# Connectors.net
KiCad netlist of a schematic drawn in Altium Designer
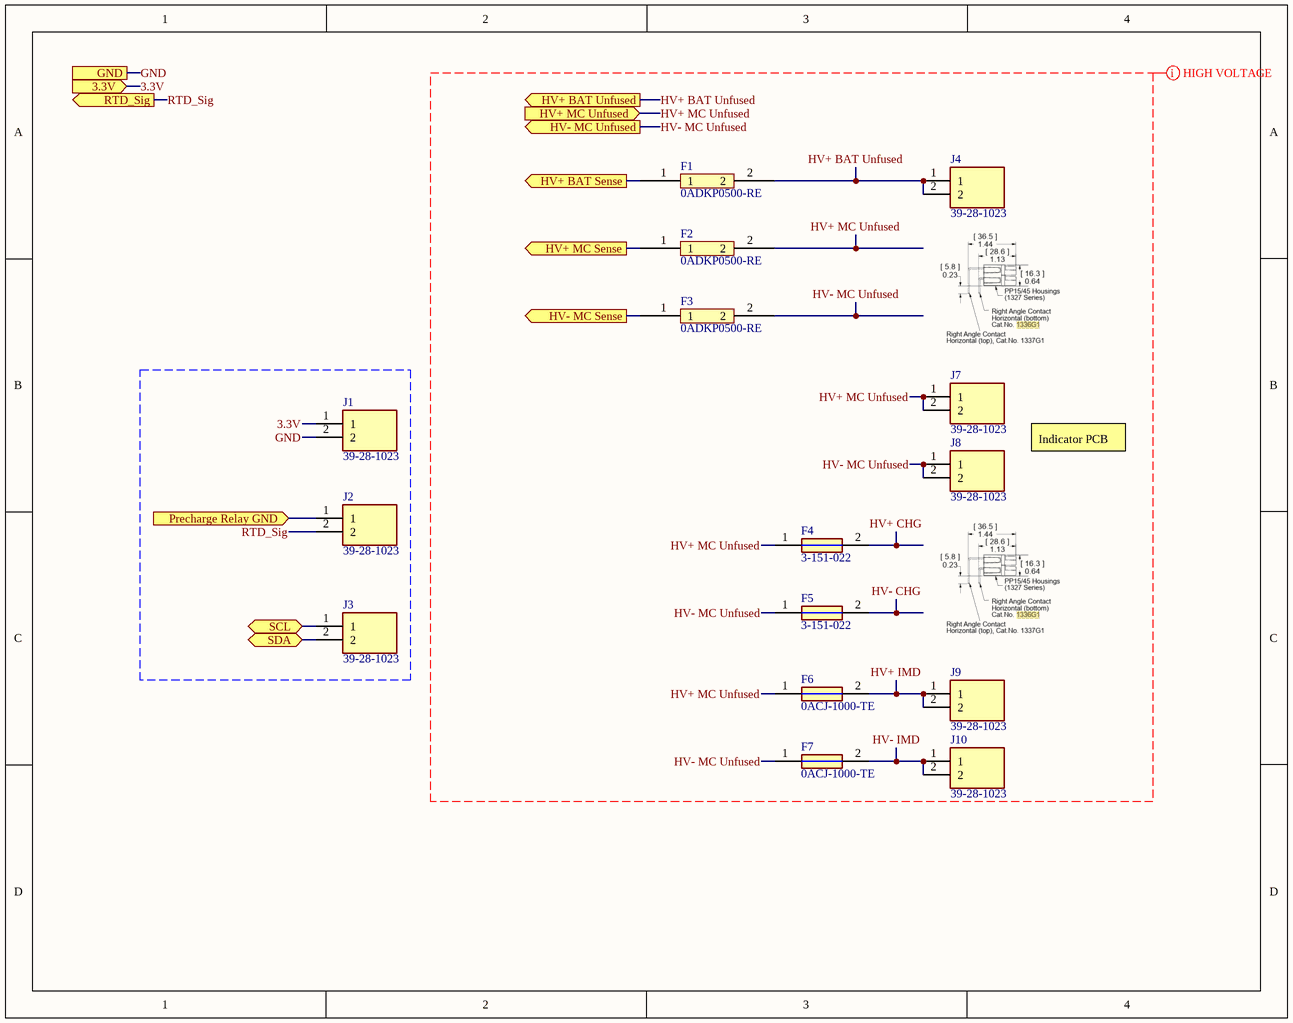
[diagram p0: Connectors.SchDoc]

(export (version "E")
  (design (tool "Eeschema 10.0.6"))
  (components
    (comp (ref "F1")
      (value "0ADKP0500-RE")
      (footprint "0ADKP0500-RE")
      (description "Fuse")
      (libsource (lib "SamacSys") (part "0ADKP0500-RE"))
    )
    (comp (ref "F2")
      (value "0ADKP0500-RE")
      (footprint "0ADKP0500-RE")
      (description "Fuse")
      (libsource (lib "SamacSys") (part "0ADKP0500-RE"))
    )
    (comp (ref "F3")
      (value "0ADKP0500-RE")
      (footprint "0ADKP0500-RE")
      (description "Fuse")
      (libsource (lib "SamacSys") (part "0ADKP0500-RE"))
    )
    (comp (ref "F4")
      (value "3-151-022")
      (footprint "SamacSys:3151022")
      (description "Fuse")
      (libsource (lib "SamacSys") (part "3-151-022"))
    )
    (comp (ref "F5")
      (value "3-151-022")
      (footprint "SamacSys:3151022")
      (description "Fuse")
      (libsource (lib "SamacSys") (part "3-151-022"))
    )
    (comp (ref "F6")
      (value "0ACJ-1000-TE")
      (footprint "FUSC13250X555N")
      (description "Fuse")
      (fields (field (name "MOUSER PART NUMBER") "530-0ACJ-1000-TE"))
      (libsource (lib "SamacSys") (part "0ACJ-1000-TE"))
    )
    (comp (ref "F7")
      (value "0ACJ-1000-TE")
      (footprint "FUSC13250X555N")
      (description "Fuse")
      (fields (field (name "MOUSER PART NUMBER") "530-0ACJ-1000-TE"))
      (libsource (lib "SamacSys") (part "0ACJ-1000-TE"))
    )
    (comp (ref "J1")
      (value "39-28-1023")
      (footprint "SamacSys:39-28-1023")
      (description "Connector")
      (fields (field (name "MOUSER PART NUMBER") "538-39-28-1023"))
      (libsource (lib "SamacSys") (part "39-28-1023"))
    )
    (comp (ref "J2")
      (value "39-28-1023")
      (footprint "SamacSys:39-28-1023")
      (description "Connector")
      (fields (field (name "MOUSER PART NUMBER") "538-39-28-1023"))
      (libsource (lib "SamacSys") (part "39-28-1023"))
    )
    (comp (ref "J3")
      (value "39-28-1023")
      (footprint "SamacSys:39-28-1023")
      (description "Connector")
      (fields (field (name "MOUSER PART NUMBER") "538-39-28-1023"))
      (libsource (lib "SamacSys") (part "39-28-1023"))
    )
    (comp (ref "J4")
      (value "39-28-1023")
      (footprint "SamacSys:39-28-1023")
      (description "Connector")
      (fields (field (name "MOUSER PART NUMBER") "538-39-28-1023"))
      (libsource (lib "SamacSys") (part "39-28-1023"))
    )
    (comp (ref "J7")
      (value "39-28-1023")
      (footprint "SamacSys:39-28-1023")
      (description "Connector")
      (fields (field (name "MOUSER PART NUMBER") "538-39-28-1023"))
      (libsource (lib "SamacSys") (part "39-28-1023"))
    )
    (comp (ref "J8")
      (value "39-28-1023")
      (footprint "SamacSys:39-28-1023")
      (description "Connector")
      (fields (field (name "MOUSER PART NUMBER") "538-39-28-1023"))
      (libsource (lib "SamacSys") (part "39-28-1023"))
    )
    (comp (ref "J9")
      (value "39-28-1023")
      (footprint "SamacSys:39-28-1023")
      (description "Connector")
      (fields (field (name "MOUSER PART NUMBER") "538-39-28-1023"))
      (libsource (lib "SamacSys") (part "39-28-1023"))
    )
    (comp (ref "J10")
      (value "39-28-1023")
      (footprint "SamacSys:39-28-1023")
      (description "Connector")
      (fields (field (name "MOUSER PART NUMBER") "538-39-28-1023"))
      (libsource (lib "SamacSys") (part "39-28-1023"))
    )
  )
  (nets
    (net (code "1") (name "/3.3V") (class "Default")
      (node (ref "J1") (pin "1") (pinfunction "1_1") (pintype "passive"))
    )
    (net (code "2") (name "/GND") (class "Default")
      (node (ref "J1") (pin "2") (pinfunction "2_2") (pintype "passive"))
    )
    (net (code "3") (name "/HV+ BAT Sense") (class "Default")
      (node (ref "F1") (pin "1") (pinfunction "1_1") (pintype "passive"))
    )
    (net (code "4") (name "/HV+ BAT Unfused") (class "Default")
      (node (ref "F1") (pin "2") (pinfunction "2_2") (pintype "passive"))
      (node (ref "J4") (pin "1") (pinfunction "1_1") (pintype "passive"))
      (node (ref "J4") (pin "2") (pinfunction "2_2") (pintype "passive"))
    )
    (net (code "5") (name "/HV+ CHG") (class "Default")
      (node (ref "F4") (pin "2") (pinfunction "2_2") (pintype "passive"))
    )
    (net (code "6") (name "/HV+ IMD") (class "Default")
      (node (ref "F6") (pin "2") (pinfunction "2_2") (pintype "passive"))
      (node (ref "J9") (pin "1") (pinfunction "1_1") (pintype "passive"))
      (node (ref "J9") (pin "2") (pinfunction "2_2") (pintype "passive"))
    )
    (net (code "7") (name "/HV+ MC Sense") (class "Default")
      (node (ref "F2") (pin "1") (pinfunction "1_1") (pintype "passive"))
    )
    (net (code "8") (name "/HV+ MC Unfused") (class "Default")
      (node (ref "F2") (pin "2") (pinfunction "2_2") (pintype "passive"))
      (node (ref "F4") (pin "1") (pinfunction "1_1") (pintype "passive"))
      (node (ref "F6") (pin "1") (pinfunction "1_1") (pintype "passive"))
      (node (ref "J7") (pin "1") (pinfunction "1_1") (pintype "passive"))
      (node (ref "J7") (pin "2") (pinfunction "2_2") (pintype "passive"))
    )
    (net (code "9") (name "/HV- CHG") (class "Default")
      (node (ref "F5") (pin "2") (pinfunction "2_2") (pintype "passive"))
    )
    (net (code "10") (name "/HV- IMD") (class "Default")
      (node (ref "F7") (pin "2") (pinfunction "2_2") (pintype "passive"))
      (node (ref "J10") (pin "1") (pinfunction "1_1") (pintype "passive"))
      (node (ref "J10") (pin "2") (pinfunction "2_2") (pintype "passive"))
    )
    (net (code "11") (name "/HV- MC Sense") (class "Default")
      (node (ref "F3") (pin "1") (pinfunction "1_1") (pintype "passive"))
    )
    (net (code "12") (name "/HV- MC Unfused") (class "Default")
      (node (ref "F3") (pin "2") (pinfunction "2_2") (pintype "passive"))
      (node (ref "F5") (pin "1") (pinfunction "1_1") (pintype "passive"))
      (node (ref "F7") (pin "1") (pinfunction "1_1") (pintype "passive"))
      (node (ref "J8") (pin "1") (pinfunction "1_1") (pintype "passive"))
      (node (ref "J8") (pin "2") (pinfunction "2_2") (pintype "passive"))
    )
    (net (code "13") (name "/Precharge Relay GND") (class "Default")
      (node (ref "J2") (pin "1") (pinfunction "1_1") (pintype "passive"))
    )
    (net (code "14") (name "/RTD_Sig") (class "Default")
      (node (ref "J2") (pin "2") (pinfunction "2_2") (pintype "passive"))
    )
    (net (code "15") (name "/SCL") (class "Default")
      (node (ref "J3") (pin "1") (pinfunction "1_1") (pintype "passive"))
    )
    (net (code "16") (name "/SDA") (class "Default")
      (node (ref "J3") (pin "2") (pinfunction "2_2") (pintype "passive"))
    )
  )
)
